# sensor_module.net
KiCad netlist of a schematic drawn in Altium Designer
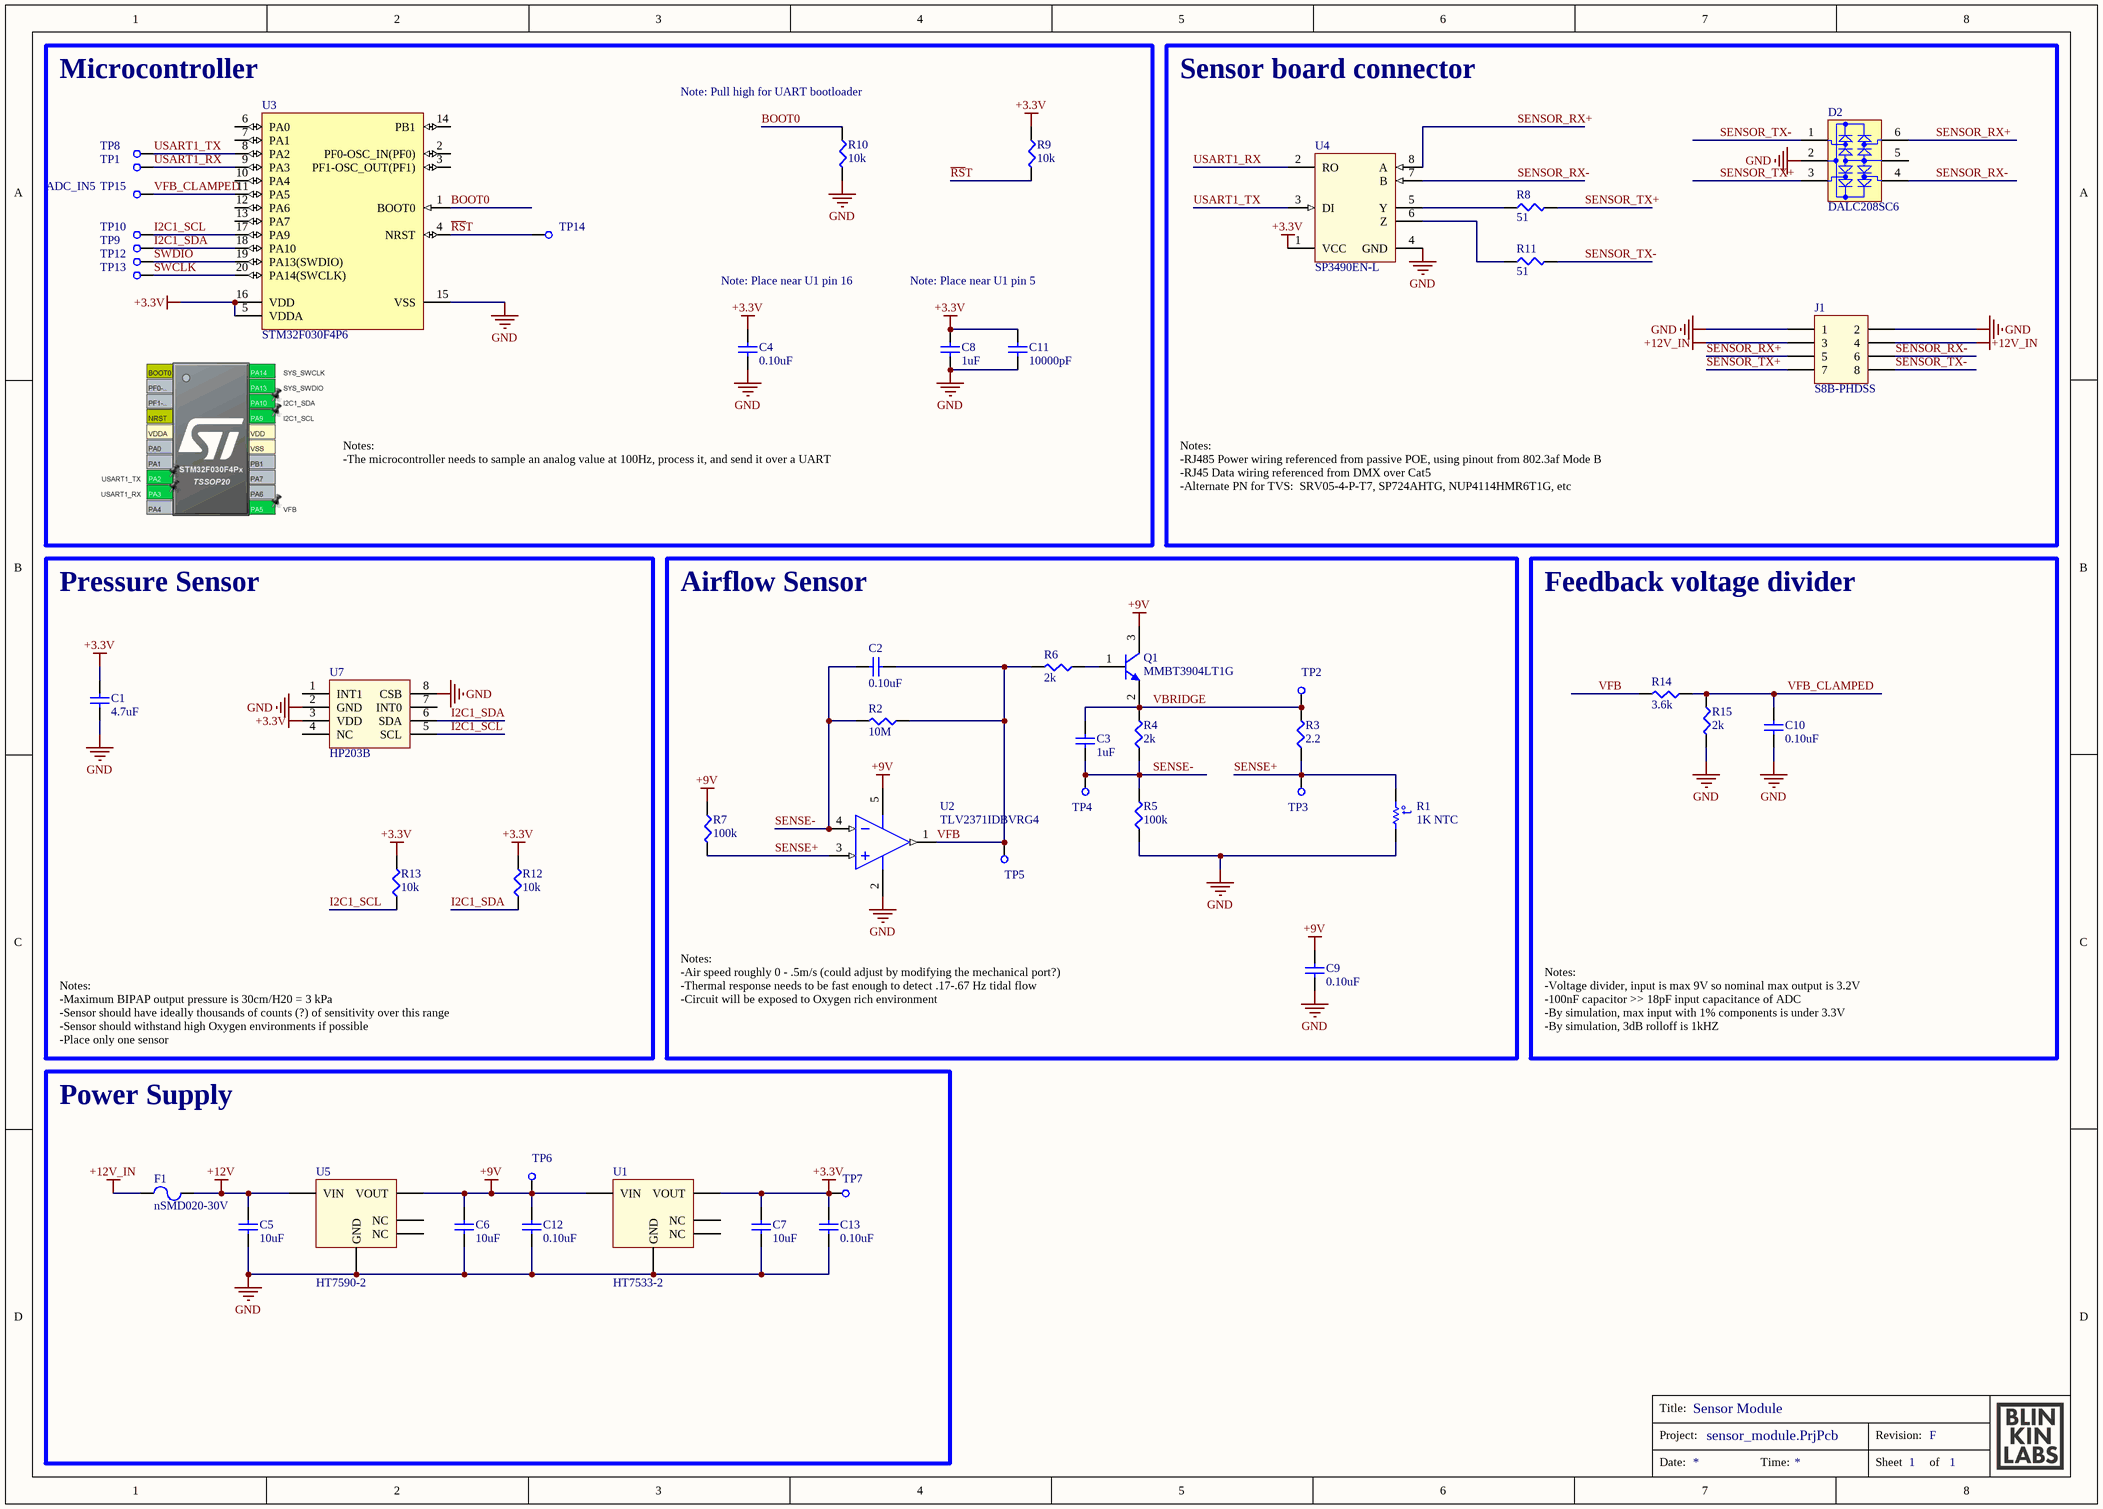
[diagram p0: sensor_module.SchDoc]

(export (version "E")
  (design (tool "Eeschema 10.0.6"))
  (components
    (comp (ref "C1")
      (value "4.7uF")
      (footprint "CAPC1005X06N")
      (description "CAP CER 4.7UF 6.3V X5R 0402")
      (fields
        (field (name "DIGI-KEY PART NUMBER") "490-5915-1-ND")
        (field (name "MANUFACTURER") "Murata Electronics North America")
      )
      (libsource (lib "cap_murata") (part "CAPACITOR"))
    )
    (comp (ref "C2")
      (value "0.10uF")
      (footprint "CAPC1005X06N")
      (description "CAP CER 0.1UF 10V X5R 0402")
      (fields
        (field (name "DIGI-KEY PART NUMBER") "490-10009-1-ND")
        (field (name "MANUFACTURER") "Murata Electronics North America")
      )
      (libsource (lib "cap_murata") (part "CAPACITOR"))
    )
    (comp (ref "C3")
      (value "1uF")
      (footprint "CAPC1005X06N")
      (description "CAP CER 1UF 10V X5R 0402")
      (fields
        (field (name "DIGI-KEY PART NUMBER") "490-5409-1-ND")
        (field (name "MANUFACTURER") "Murata Electronics North America")
      )
      (libsource (lib "cap_murata") (part "CAPACITOR"))
    )
    (comp (ref "C4")
      (value "0.10uF")
      (footprint "CAPC1005X06N")
      (description "CAP CER 0.1UF 10V X5R 0402")
      (fields
        (field (name "DIGI-KEY PART NUMBER") "490-10009-1-ND")
        (field (name "MANUFACTURER") "Murata Electronics North America")
      )
      (libsource (lib "cap_murata") (part "CAPACITOR"))
    )
    (comp (ref "C5")
      (value "10uF")
      (footprint "CAPC2012X10L")
      (description "CAP CER 10UF 16V X5R 0805")
      (fields
        (field (name "DIGI-KEY PART NUMBER") "490-6474-1-ND")
        (field (name "MANUFACTURER") "Murata Electronics North America")
      )
      (libsource (lib "cap_murata") (part "CAPACITOR"))
    )
    (comp (ref "C6")
      (value "10uF")
      (footprint "CAPC2012X10L")
      (description "CAP CER 10UF 16V X5R 0805")
      (fields
        (field (name "DIGI-KEY PART NUMBER") "490-6474-1-ND")
        (field (name "MANUFACTURER") "Murata Electronics North America")
      )
      (libsource (lib "cap_murata") (part "CAPACITOR"))
    )
    (comp (ref "C7")
      (value "10uF")
      (footprint "CAPC2012X10L")
      (description "CAP CER 10UF 16V X5R 0805")
      (fields
        (field (name "DIGI-KEY PART NUMBER") "490-6474-1-ND")
        (field (name "MANUFACTURER") "Murata Electronics North America")
      )
      (libsource (lib "cap_murata") (part "CAPACITOR"))
    )
    (comp (ref "C8")
      (value "1uF")
      (footprint "CAPC1005X06N")
      (description "CAP CER 1UF 10V X5R 0402")
      (fields
        (field (name "DIGI-KEY PART NUMBER") "490-5409-1-ND")
        (field (name "MANUFACTURER") "Murata Electronics North America")
      )
      (libsource (lib "cap_murata") (part "CAPACITOR"))
    )
    (comp (ref "C9")
      (value "0.10uF")
      (footprint "CAPC1005X06N")
      (description "CAP CER 0.1UF 10V X5R 0402")
      (fields
        (field (name "DIGI-KEY PART NUMBER") "490-10009-1-ND")
        (field (name "MANUFACTURER") "Murata Electronics North America")
      )
      (libsource (lib "cap_murata") (part "CAPACITOR"))
    )
    (comp (ref "C10")
      (value "0.10uF")
      (footprint "CAPC1005X06N")
      (description "CAP CER 0.1UF 10V X5R 0402")
      (fields
        (field (name "DIGI-KEY PART NUMBER") "490-10009-1-ND")
        (field (name "MANUFACTURER") "Murata Electronics North America")
      )
      (libsource (lib "cap_murata") (part "CAPACITOR"))
    )
    (comp (ref "C11")
      (value "10000pF")
      (footprint "CAPC1005X06N")
      (description "CAP CER 10000PF 16V X5R 0402")
      (fields
        (field (name "DIGI-KEY PART NUMBER") "490-6309-1-ND")
        (field (name "MANUFACTURER") "Murata Electronics North America")
      )
      (libsource (lib "cap_murata") (part "CAPACITOR"))
    )
    (comp (ref "C12")
      (value "0.10uF")
      (footprint "CAPC1005X06N")
      (description "CAP CER 0.1UF 10V X5R 0402")
      (fields
        (field (name "DIGI-KEY PART NUMBER") "490-10009-1-ND")
        (field (name "MANUFACTURER") "Murata Electronics North America")
      )
      (libsource (lib "cap_murata") (part "CAPACITOR"))
    )
    (comp (ref "C13")
      (value "0.10uF")
      (footprint "CAPC1005X06N")
      (description "CAP CER 0.1UF 10V X5R 0402")
      (fields
        (field (name "DIGI-KEY PART NUMBER") "490-10009-1-ND")
        (field (name "MANUFACTURER") "Murata Electronics North America")
      )
      (libsource (lib "cap_murata") (part "CAPACITOR"))
    )
    (comp (ref "D2")
      (value "DALC208SC6")
      (footprint "STM-SOT23-6L_V")
      (description "Low Capacitance Diode Array, 1 uA, 1.2 V, -55 to 150 degC, 6-Pin SOT23-6L, RoHS, Tape and Reel")
      (fields (field (name "MANUFACTURER") "STMicroelectronics"))
      (libsource (lib "Altium Content Vault") (part "STM-DALC208-SOT23-6L-6"))
    )
    (comp (ref "F1")
      (value "nSMD020-30V")
      (footprint "SEAANDLAND_1206")
      (description "Surface Mount Fuses 30V 100A 200mA 460mA 1206 RoHS")
      (fields
        (field (name "MANUFACTURER") "Sea & Land Electronic Corp")
        (field (name "PARTNUMBER") "NSMD020-30V")
      )
      (libsource (lib "Blinkinlabs") (part "nSMD020-30V"))
    )
    (comp (ref "J1")
      (value "S8B-PHDSS")
      (footprint "S8B-PHDSS")
      (description "CONN HEADER R/A 8POS 2MM")
      (fields (field (name "MANUFACTURER") "JST"))
      (libsource (lib "Blinkinlabs") (part "S8B-PHDSS"))
    )
    (comp (ref "Q1")
      (value "MMBT3904LT1G")
      (footprint "ONSC-SOT-23-3-318-08_V")
      (description "General Purpose Transistor, NPN Silicon, 3-Pin SOT-23, Pb-Free, Tape and Reel")
      (fields (field (name "MANUFACTURER") "On Semiconductor"))
      (libsource (lib "Altium Content Vault") (part "ONSC-NPN-B1E2C3-3"))
    )
    (comp (ref "R1")
      (value "1K NTC")
      (footprint "MURA-NCP18XH103F03RB-2_V")
      (description "NTC Thermistor, 10 KOhm, +/- 1%, 0.1 W, -40 to 125 degC, 0603 (1608 Metric), RoHS, Tape and Reel")
      (fields (field (name "MANUFACTURER") "Murata"))
      (libsource (lib "Altium Content Vault") (part "MURA-NCP18XH103F03RB-2"))
    )
    (comp (ref "R2")
      (value "10M")
      (footprint "ERJ2G(0402)_N")
      (description "RES SMD 10M OHM 5% 1/10W 0402")
      (fields (field (name "PART NUMBER") "ERJ-2GEJ106X") (field (name "DIGI-KEY PART NUMBER") "P10MJCT-ND"))
      (libsource (lib "res_panasonic_erj_xls") (part "RESISTOR"))
    )
    (comp (ref "R3")
      (value "2.2")
      (footprint "ERJ2G(0402)_N")
      (description "RES SMD 2.2 OHM 5% 1/10W 0402")
      (fields (field (name "PARTNUMBER") "ERJ-2GEJ2R2X") (field (name "DIGI-KEY PART NUMBER") "P2.2JCT-ND"))
      (libsource (lib "res_panasonic_erj_xls") (part "RESISTOR"))
    )
    (comp (ref "R4")
      (value "2k")
      (footprint "ERJ2G(0402)_N")
      (description "RES SMD 2K OHM 1% 1/10W 0402")
      (fields
        (field (name "PART NUMBER") "ERJ-2RKF2001X")
        (field (name "DIGI-KEY PART NUMBER") "P2.00KLCT-ND")
      )
      (libsource (lib "res_panasonic_erj_xls") (part "RESISTOR"))
    )
    (comp (ref "R5")
      (value "100k")
      (footprint "ERJ2G(0402)_N")
      (description "RES SMD 100K OHM 1% 1/10W 0402")
      (fields
        (field (name "PART NUMBER") "ERJ-2RKF1003X")
        (field (name "DIGI-KEY PART NUMBER") "P100KLCT-ND")
      )
      (libsource (lib "res_panasonic_erj_xls") (part "RESISTOR"))
    )
    (comp (ref "R6")
      (value "2k")
      (footprint "ERJ2G(0402)_N")
      (description "RES SMD 2K OHM 1% 1/10W 0402")
      (fields
        (field (name "PART NUMBER") "ERJ-2RKF2001X")
        (field (name "DIGI-KEY PART NUMBER") "P2.00KLCT-ND")
      )
      (libsource (lib "res_panasonic_erj_xls") (part "RESISTOR"))
    )
    (comp (ref "R7")
      (value "100k")
      (footprint "ERJ2G(0402)_N")
      (description "RES SMD 100K OHM 1% 1/10W 0402")
      (fields
        (field (name "PART NUMBER") "ERJ-2RKF1003X")
        (field (name "DIGI-KEY PART NUMBER") "P100KLCT-ND")
      )
      (libsource (lib "res_panasonic_erj_xls") (part "RESISTOR"))
    )
    (comp (ref "R8")
      (value "51")
      (footprint "ERJ2G(0402)_N")
      (description "RES SMD 51 OHM 5% 1/10W 0402")
      (fields (field (name "PART NUMBER") "ERJ-2GEJ510X") (field (name "DIGI-KEY PART NUMBER") "P51JCT-ND"))
      (libsource (lib "res_panasonic_erj_xls") (part "RESISTOR"))
    )
    (comp (ref "R9")
      (value "10k")
      (footprint "ERJ2G(0402)_N")
      (description "RES SMD 10K OHM 5% 1/10W 0402")
      (fields (field (name "PART NUMBER") "ERJ-2GEJ103X") (field (name "DIGI-KEY PART NUMBER") "P10KJCT-ND"))
      (libsource (lib "res_panasonic_erj_xls") (part "RESISTOR"))
    )
    (comp (ref "R10")
      (value "10k")
      (footprint "ERJ2G(0402)_N")
      (description "RES SMD 10K OHM 5% 1/10W 0402")
      (fields (field (name "PART NUMBER") "ERJ-2GEJ103X") (field (name "DIGI-KEY PART NUMBER") "P10KJCT-ND"))
      (libsource (lib "res_panasonic_erj_xls") (part "RESISTOR"))
    )
    (comp (ref "R11")
      (value "51")
      (footprint "ERJ2G(0402)_N")
      (description "RES SMD 51 OHM 5% 1/10W 0402")
      (fields (field (name "PART NUMBER") "ERJ-2GEJ510X") (field (name "DIGI-KEY PART NUMBER") "P51JCT-ND"))
      (libsource (lib "res_panasonic_erj_xls") (part "RESISTOR"))
    )
    (comp (ref "R12")
      (value "10k")
      (footprint "ERJ2G(0402)_N")
      (description "RES SMD 10K OHM 5% 1/10W 0402")
      (fields (field (name "PART NUMBER") "ERJ-2GEJ103X") (field (name "DIGI-KEY PART NUMBER") "P10KJCT-ND"))
      (libsource (lib "res_panasonic_erj_xls") (part "RESISTOR"))
    )
    (comp (ref "R13")
      (value "10k")
      (footprint "ERJ2G(0402)_N")
      (description "RES SMD 10K OHM 5% 1/10W 0402")
      (fields (field (name "PART NUMBER") "ERJ-2GEJ103X") (field (name "DIGI-KEY PART NUMBER") "P10KJCT-ND"))
      (libsource (lib "res_panasonic_erj_xls") (part "RESISTOR"))
    )
    (comp (ref "R14")
      (value "3.6k")
      (footprint "ERJ2G(0402)_N")
      (description "RES SMD 3.6K OHM 1% 1/10W 0402")
      (fields
        (field (name "PART NUMBER") "ERJ-2RKF3601X")
        (field (name "DIGI-KEY PART NUMBER") "P3.60KLCT-ND")
      )
      (libsource (lib "res_panasonic_erj_xls") (part "RESISTOR"))
    )
    (comp (ref "R15")
      (value "2k")
      (footprint "ERJ2G(0402)_N")
      (description "RES SMD 2K OHM 1% 1/10W 0402")
      (fields
        (field (name "PART NUMBER") "ERJ-2RKF2001X")
        (field (name "DIGI-KEY PART NUMBER") "P2.00KLCT-ND")
      )
      (libsource (lib "res_panasonic_erj_xls") (part "RESISTOR"))
    )
    (comp (ref "TP1")
      (value "TEST_POINT")
      (footprint "TP-SMD-1mm")
      (description "Test point")
      (libsource (lib "Blinkinlabs") (part "TEST_POINT"))
    )
    (comp (ref "TP2")
      (value "TEST_POINT")
      (footprint "TP-SMD-1mm")
      (description "Test point")
      (libsource (lib "Blinkinlabs") (part "TEST_POINT"))
    )
    (comp (ref "TP3")
      (value "TEST_POINT")
      (footprint "TP-SMD-1mm")
      (description "Test point")
      (libsource (lib "Blinkinlabs") (part "TEST_POINT"))
    )
    (comp (ref "TP4")
      (value "TEST_POINT")
      (footprint "TP-SMD-1mm")
      (description "Test point")
      (libsource (lib "Blinkinlabs") (part "TEST_POINT"))
    )
    (comp (ref "TP5")
      (value "TEST_POINT")
      (footprint "TP-SMD-1mm")
      (description "Test point")
      (libsource (lib "Blinkinlabs") (part "TEST_POINT"))
    )
    (comp (ref "TP6")
      (value "TEST_POINT")
      (footprint "TP-SMD-1mm")
      (description "Test point")
      (libsource (lib "Blinkinlabs") (part "TEST_POINT"))
    )
    (comp (ref "TP7")
      (value "TEST_POINT")
      (footprint "TP-SMD-1mm")
      (description "Test point")
      (libsource (lib "Blinkinlabs") (part "TEST_POINT"))
    )
    (comp (ref "TP8")
      (value "TEST_POINT")
      (footprint "TP-SMD-1mm")
      (description "Test point")
      (libsource (lib "Blinkinlabs") (part "TEST_POINT"))
    )
    (comp (ref "TP9")
      (value "TEST_POINT")
      (footprint "TP-SMD-1mm")
      (description "Test point")
      (libsource (lib "Blinkinlabs") (part "TEST_POINT"))
    )
    (comp (ref "TP10")
      (value "TEST_POINT")
      (footprint "TP-SMD-1mm")
      (description "Test point")
      (libsource (lib "Blinkinlabs") (part "TEST_POINT"))
    )
    (comp (ref "TP12")
      (value "TEST_POINT")
      (footprint "TP-SMD-1mm")
      (description "Test point")
      (libsource (lib "Blinkinlabs") (part "TEST_POINT"))
    )
    (comp (ref "TP13")
      (value "TEST_POINT")
      (footprint "TP-SMD-1mm")
      (description "Test point")
      (libsource (lib "Blinkinlabs") (part "TEST_POINT"))
    )
    (comp (ref "TP14")
      (value "TEST_POINT")
      (footprint "TP-SMD-1mm")
      (description "Test point")
      (libsource (lib "Blinkinlabs") (part "TEST_POINT"))
    )
    (comp (ref "TP15")
      (value "TEST_POINT")
      (footprint "TP-SMD-1mm")
      (description "Test point")
      (libsource (lib "Blinkinlabs") (part "TEST_POINT"))
    )
    (comp (ref "U1")
      (value "HT7533-2")
      (footprint "SOT95P280X145-5N")
      (description "3.3V 100mA TinyPower LDO")
      (fields (field (name "MANUFACTURER") "Holtek"))
      (libsource (lib "Blinkinlabs") (part "HT7533-2"))
    )
    (comp (ref "U2")
      (value "TLV2371IDBVRG4")
      (footprint "TI-DBV5_N")
      (fields (field (name "MANUFACTURER") "Texas Instruments"))
      (libsource (lib "Altium Content Vault") (part "TI-TLV2XX1DBV5"))
    )
    (comp (ref "U3")
      (value "STM32F030F4P6")
      (footprint "STM-TSSOP20_L")
      (libsource (lib "Altium Content Vault") (part "MC-ARM-STM32F030-IL20"))
    )
    (comp (ref "U4")
      (value "SP3490EN-L")
      (footprint "SOIC127P600X175-8N-2")
      (description "+3.3V Low Power Full-Duplex RS-485 Transceivers with 10Mbps Data Rate")
      (fields (field (name "MANUFACTURER") "Exar"))
      (libsource (lib "Blinkinlabs") (part "SP3490EN-L"))
    )
    (comp (ref "U5")
      (value "HT7590-2")
      (footprint "SOT95P280X145-5N")
      (description "9V 100mA TinyPower LDO")
      (fields (field (name "MANUFACTURER") "Holtek"))
      (libsource (lib "Blinkinlabs") (part "HT7590-2"))
    )
    (comp (ref "U7")
      (value "HP203B")
      (footprint "HP203B")
      (description "PRECISION BAROMETER AND ALTIMETER SENSOR")
      (fields (field (name "MANUFACTURER") "HopeRF"))
      (libsource (lib "Blinkinlabs") (part "HP203B"))
    )
  )
  (nets
    (net (code "1") (name "+3.3V") (class "Default")
      (node (ref "C1") (pin "2") (pinfunction "2_2") (pintype "passive"))
      (node (ref "C11") (pin "1") (pinfunction "1_1") (pintype "passive"))
      (node (ref "C13") (pin "2") (pinfunction "2_2") (pintype "passive"))
      (node (ref "C4") (pin "2") (pinfunction "2_2") (pintype "passive"))
      (node (ref "C7") (pin "1") (pinfunction "1_1") (pintype "passive"))
      (node (ref "C8") (pin "2") (pinfunction "2_2") (pintype "passive"))
      (node (ref "R12") (pin "2") (pinfunction "2_2") (pintype "passive"))
      (node (ref "R13") (pin "2") (pinfunction "2_2") (pintype "passive"))
      (node (ref "R9") (pin "1") (pinfunction "1_1") (pintype "passive"))
      (node (ref "TP7") (pin "1") (pinfunction "TP_1") (pintype "passive"))
      (node (ref "U1") (pin "3") (pinfunction "VOUT_3") (pintype "passive"))
      (node (ref "U3") (pin "16") (pinfunction "VDD_16") (pintype "power_in"))
      (node (ref "U3") (pin "5") (pinfunction "VDDA_5") (pintype "power_in"))
      (node (ref "U4") (pin "1") (pinfunction "VCC_1") (pintype "passive"))
      (node (ref "U7") (pin "3") (pinfunction "VDD_3") (pintype "power_in"))
    )
    (net (code "2") (name "+9V") (class "Default")
      (node (ref "C12") (pin "2") (pinfunction "2_2") (pintype "passive"))
      (node (ref "C6") (pin "1") (pinfunction "1_1") (pintype "passive"))
      (node (ref "C9") (pin "2") (pinfunction "2_2") (pintype "passive"))
      (node (ref "Q1") (pin "3") (pinfunction "C_3") (pintype "passive"))
      (node (ref "R7") (pin "1") (pinfunction "1_1") (pintype "passive"))
      (node (ref "TP6") (pin "1") (pinfunction "TP_1") (pintype "passive"))
      (node (ref "U1") (pin "2") (pinfunction "VIN_2") (pintype "passive"))
      (node (ref "U2") (pin "5") (pinfunction "VDD_5") (pintype "power_in"))
      (node (ref "U5") (pin "3") (pinfunction "VOUT_3") (pintype "passive"))
    )
    (net (code "3") (name "+12V") (class "Default")
      (node (ref "C5") (pin "1") (pinfunction "1_1") (pintype "passive"))
      (node (ref "F1") (pin "2") (pinfunction "2_2") (pintype "passive"))
      (node (ref "U5") (pin "2") (pinfunction "VIN_2") (pintype "passive"))
    )
    (net (code "4") (name "+12V_IN") (class "Default")
      (node (ref "F1") (pin "1") (pinfunction "1_1") (pintype "passive"))
      (node (ref "J1") (pin "3") (pinfunction "3_3") (pintype "passive"))
      (node (ref "J1") (pin "4") (pinfunction "4_4") (pintype "passive"))
    )
    (net (code "5") (name "/BOOT0") (class "Default")
      (node (ref "R10") (pin "1") (pinfunction "1_1") (pintype "passive"))
      (node (ref "U3") (pin "1") (pinfunction "BOOT0_1") (pintype "input"))
    )
    (net (code "6") (name "/I2C1_SCL") (class "Default")
      (node (ref "R13") (pin "1") (pinfunction "1_1") (pintype "passive"))
      (node (ref "TP10") (pin "1") (pinfunction "TP_1") (pintype "passive"))
      (node (ref "U3") (pin "17") (pinfunction "PA9_17") (pintype "bidirectional"))
      (node (ref "U7") (pin "5") (pinfunction "SCL_5") (pintype "passive"))
    )
    (net (code "7") (name "/I2C1_SDA") (class "Default")
      (node (ref "R12") (pin "1") (pinfunction "1_1") (pintype "passive"))
      (node (ref "TP9") (pin "1") (pinfunction "TP_1") (pintype "passive"))
      (node (ref "U3") (pin "18") (pinfunction "PA10_18") (pintype "bidirectional"))
      (node (ref "U7") (pin "6") (pinfunction "SDA_6") (pintype "passive"))
    )
    (net (code "8") (name "/SENSE+") (class "Default")
      (node (ref "R1") (pin "2") (pinfunction "2_2") (pintype "passive"))
      (node (ref "R3") (pin "1") (pinfunction "1_1") (pintype "passive"))
      (node (ref "R7") (pin "2") (pinfunction "2_2") (pintype "passive"))
      (node (ref "TP3") (pin "1") (pinfunction "TP_1") (pintype "passive"))
      (node (ref "U2") (pin "3") (pinfunction "IN+_3") (pintype "input"))
    )
    (net (code "9") (name "/SENSE-") (class "Default")
      (node (ref "C2") (pin "2") (pinfunction "2_2") (pintype "passive"))
      (node (ref "C3") (pin "2") (pinfunction "2_2") (pintype "passive"))
      (node (ref "R2") (pin "2") (pinfunction "2_2") (pintype "passive"))
      (node (ref "R4") (pin "1") (pinfunction "1_1") (pintype "passive"))
      (node (ref "R5") (pin "2") (pinfunction "2_2") (pintype "passive"))
      (node (ref "TP4") (pin "1") (pinfunction "TP_1") (pintype "passive"))
      (node (ref "U2") (pin "4") (pinfunction "IN-_4") (pintype "input"))
    )
    (net (code "10") (name "/SENSOR_RX+") (class "Default")
      (node (ref "D2") (pin "6") (pinfunction "I/O_4_6") (pintype "passive"))
      (node (ref "J1") (pin "5") (pinfunction "5_5") (pintype "passive"))
      (node (ref "U4") (pin "8") (pinfunction "A_8") (pintype "input"))
    )
    (net (code "11") (name "/SENSOR_RX-") (class "Default")
      (node (ref "D2") (pin "4") (pinfunction "I/O_3_4") (pintype "passive"))
      (node (ref "J1") (pin "6") (pinfunction "6_6") (pintype "passive"))
      (node (ref "U4") (pin "7") (pinfunction "B_7") (pintype "input"))
    )
    (net (code "12") (name "/SENSOR_TX+") (class "Default")
      (node (ref "D2") (pin "3") (pinfunction "I/O_2_3") (pintype "passive"))
      (node (ref "J1") (pin "7") (pinfunction "7_7") (pintype "passive"))
      (node (ref "R8") (pin "2") (pinfunction "2_2") (pintype "passive"))
    )
    (net (code "13") (name "/SENSOR_TX-") (class "Default")
      (node (ref "D2") (pin "1") (pinfunction "I/O_1_1") (pintype "passive"))
      (node (ref "J1") (pin "8") (pinfunction "8_8") (pintype "passive"))
      (node (ref "R11") (pin "2") (pinfunction "2_2") (pintype "passive"))
    )
    (net (code "14") (name "/SWCLK") (class "Default")
      (node (ref "TP13") (pin "1") (pinfunction "TP_1") (pintype "passive"))
      (node (ref "U3") (pin "20") (pinfunction "PA14(SWCLK)_20") (pintype "bidirectional"))
    )
    (net (code "15") (name "/SWDIO") (class "Default")
      (node (ref "TP12") (pin "1") (pinfunction "TP_1") (pintype "passive"))
      (node (ref "U3") (pin "19") (pinfunction "PA13(SWDIO)_19") (pintype "bidirectional"))
    )
    (net (code "16") (name "/USART1_RX") (class "Default")
      (node (ref "TP1") (pin "1") (pinfunction "TP_1") (pintype "passive"))
      (node (ref "U3") (pin "9") (pinfunction "PA3_9") (pintype "bidirectional"))
      (node (ref "U4") (pin "2") (pinfunction "RO_2") (pintype "passive"))
    )
    (net (code "17") (name "/USART1_TX") (class "Default")
      (node (ref "TP8") (pin "1") (pinfunction "TP_1") (pintype "passive"))
      (node (ref "U3") (pin "8") (pinfunction "PA2_8") (pintype "bidirectional"))
      (node (ref "U4") (pin "3") (pinfunction "DI_3") (pintype "input"))
    )
    (net (code "18") (name "/VBRIDGE") (class "Default")
      (node (ref "C3") (pin "1") (pinfunction "1_1") (pintype "passive"))
      (node (ref "Q1") (pin "2") (pinfunction "E_2") (pintype "passive"))
      (node (ref "R3") (pin "2") (pinfunction "2_2") (pintype "passive"))
      (node (ref "R4") (pin "2") (pinfunction "2_2") (pintype "passive"))
      (node (ref "TP2") (pin "1") (pinfunction "TP_1") (pintype "passive"))
    )
    (net (code "19") (name "/VFB") (class "Default")
      (node (ref "C2") (pin "1") (pinfunction "1_1") (pintype "passive"))
      (node (ref "R14") (pin "2") (pinfunction "2_2") (pintype "passive"))
      (node (ref "R2") (pin "1") (pinfunction "1_1") (pintype "passive"))
      (node (ref "R6") (pin "2") (pinfunction "2_2") (pintype "passive"))
      (node (ref "TP5") (pin "1") (pinfunction "TP_1") (pintype "passive"))
      (node (ref "U2") (pin "1") (pinfunction "OUT_1") (pintype "output"))
    )
    (net (code "20") (name "/VFB_CLAMPED") (class "Default")
      (node (ref "C10") (pin "1") (pinfunction "1_1") (pintype "passive"))
      (node (ref "R14") (pin "1") (pinfunction "1_1") (pintype "passive"))
      (node (ref "R15") (pin "1") (pinfunction "1_1") (pintype "passive"))
      (node (ref "TP15") (pin "1") (pinfunction "TP_1") (pintype "passive"))
      (node (ref "U3") (pin "11") (pinfunction "PA5_11") (pintype "bidirectional"))
    )
    (net (code "21") (name "/~{RS}T") (class "Default")
      (node (ref "R9") (pin "2") (pinfunction "2_2") (pintype "passive"))
      (node (ref "TP14") (pin "1") (pinfunction "TP_1") (pintype "passive"))
      (node (ref "U3") (pin "4") (pinfunction "NRST_4") (pintype "bidirectional"))
    )
    (net (code "22") (name "GND") (class "Default")
      (node (ref "C1") (pin "1") (pinfunction "1_1") (pintype "passive"))
      (node (ref "C10") (pin "2") (pinfunction "2_2") (pintype "passive"))
      (node (ref "C11") (pin "2") (pinfunction "2_2") (pintype "passive"))
      (node (ref "C12") (pin "1") (pinfunction "1_1") (pintype "passive"))
      (node (ref "C13") (pin "1") (pinfunction "1_1") (pintype "passive"))
      (node (ref "C4") (pin "1") (pinfunction "1_1") (pintype "passive"))
      (node (ref "C5") (pin "2") (pinfunction "2_2") (pintype "passive"))
      (node (ref "C6") (pin "2") (pinfunction "2_2") (pintype "passive"))
      (node (ref "C7") (pin "2") (pinfunction "2_2") (pintype "passive"))
      (node (ref "C8") (pin "1") (pinfunction "1_1") (pintype "passive"))
      (node (ref "C9") (pin "1") (pinfunction "1_1") (pintype "passive"))
      (node (ref "D2") (pin "2") (pinfunction "REF_2_2") (pintype "passive"))
      (node (ref "J1") (pin "1") (pinfunction "1_1") (pintype "passive"))
      (node (ref "J1") (pin "2") (pinfunction "2_2") (pintype "passive"))
      (node (ref "R1") (pin "1") (pinfunction "1_1") (pintype "passive"))
      (node (ref "R10") (pin "2") (pinfunction "2_2") (pintype "passive"))
      (node (ref "R15") (pin "2") (pinfunction "2_2") (pintype "passive"))
      (node (ref "R5") (pin "1") (pinfunction "1_1") (pintype "passive"))
      (node (ref "U1") (pin "1") (pinfunction "GND_1") (pintype "passive"))
      (node (ref "U2") (pin "2") (pinfunction "GND_2") (pintype "power_in"))
      (node (ref "U3") (pin "15") (pinfunction "VSS_15") (pintype "power_in"))
      (node (ref "U4") (pin "4") (pinfunction "GND_4") (pintype "passive"))
      (node (ref "U5") (pin "1") (pinfunction "GND_1") (pintype "passive"))
      (node (ref "U7") (pin "2") (pinfunction "GND_2") (pintype "power_in"))
      (node (ref "U7") (pin "8") (pinfunction "CSB_8") (pintype "passive"))
    )
    (net (code "23") (name "Net-(Q1-B)") (class "Default")
      (node (ref "Q1") (pin "1") (pinfunction "B_1") (pintype "passive"))
      (node (ref "R6") (pin "1") (pinfunction "1_1") (pintype "passive"))
    )
    (net (code "24") (name "Net-(U4-Y)") (class "Default")
      (node (ref "R8") (pin "1") (pinfunction "1_1") (pintype "passive"))
      (node (ref "U4") (pin "5") (pinfunction "Y_5") (pintype "passive"))
    )
    (net (code "25") (name "Net-(U4-Z)") (class "Default")
      (node (ref "R11") (pin "1") (pinfunction "1_1") (pintype "passive"))
      (node (ref "U4") (pin "6") (pinfunction "Z_6") (pintype "passive"))
    )
    (net (code "26") (name "unconnected-(D2-REF_1-Pad5)") (class "Default")
      (node (ref "D2") (pin "5") (pinfunction "REF_1_5") (pintype "passive"))
    )
    (net (code "27") (name "unconnected-(U1-NC-Pad4)") (class "Default")
      (node (ref "U1") (pin "4") (pinfunction "NC_4") (pintype "passive"))
    )
    (net (code "28") (name "unconnected-(U1-NC-Pad5)") (class "Default")
      (node (ref "U1") (pin "5") (pinfunction "NC_5") (pintype "passive"))
    )
    (net (code "29") (name "unconnected-(U3-PA0-Pad6)") (class "Default")
      (node (ref "U3") (pin "6") (pinfunction "PA0_6") (pintype "bidirectional"))
    )
    (net (code "30") (name "unconnected-(U3-PA1-Pad7)") (class "Default")
      (node (ref "U3") (pin "7") (pinfunction "PA1_7") (pintype "bidirectional"))
    )
    (net (code "31") (name "unconnected-(U3-PA4-Pad10)") (class "Default")
      (node (ref "U3") (pin "10") (pinfunction "PA4_10") (pintype "bidirectional"))
    )
    (net (code "32") (name "unconnected-(U3-PA6-Pad12)") (class "Default")
      (node (ref "U3") (pin "12") (pinfunction "PA6_12") (pintype "bidirectional"))
    )
    (net (code "33") (name "unconnected-(U3-PA7-Pad13)") (class "Default")
      (node (ref "U3") (pin "13") (pinfunction "PA7_13") (pintype "bidirectional"))
    )
    (net (code "34") (name "unconnected-(U3-PB1-Pad14)") (class "Default")
      (node (ref "U3") (pin "14") (pinfunction "PB1_14") (pintype "bidirectional"))
    )
    (net (code "35") (name "unconnected-(U3-PF0-OSC_IN(PF0)-Pad2)") (class "Default")
      (node (ref "U3") (pin "2") (pinfunction "PF0-OSC_IN(PF0)_2") (pintype "bidirectional"))
    )
    (net (code "36") (name "unconnected-(U3-PF1-OSC_OUT(PF1)-Pad3)") (class "Default")
      (node (ref "U3") (pin "3") (pinfunction "PF1-OSC_OUT(PF1)_3") (pintype "bidirectional"))
    )
    (net (code "37") (name "unconnected-(U5-NC-Pad4)") (class "Default")
      (node (ref "U5") (pin "4") (pinfunction "NC_4") (pintype "passive"))
    )
    (net (code "38") (name "unconnected-(U5-NC-Pad5)") (class "Default")
      (node (ref "U5") (pin "5") (pinfunction "NC_5") (pintype "passive"))
    )
    (net (code "39") (name "unconnected-(U7-INT0-Pad7)") (class "Default")
      (node (ref "U7") (pin "7") (pinfunction "INT0_7") (pintype "passive"))
    )
    (net (code "40") (name "unconnected-(U7-INT1-Pad1)") (class "Default")
      (node (ref "U7") (pin "1") (pinfunction "INT1_1") (pintype "passive"))
    )
    (net (code "41") (name "unconnected-(U7-NC-Pad4)") (class "Default")
      (node (ref "U7") (pin "4") (pinfunction "NC_4") (pintype "passive"))
    )
  )
)
